# bal2un_1.net
KiCad netlist of a schematic drawn in Altium Designer
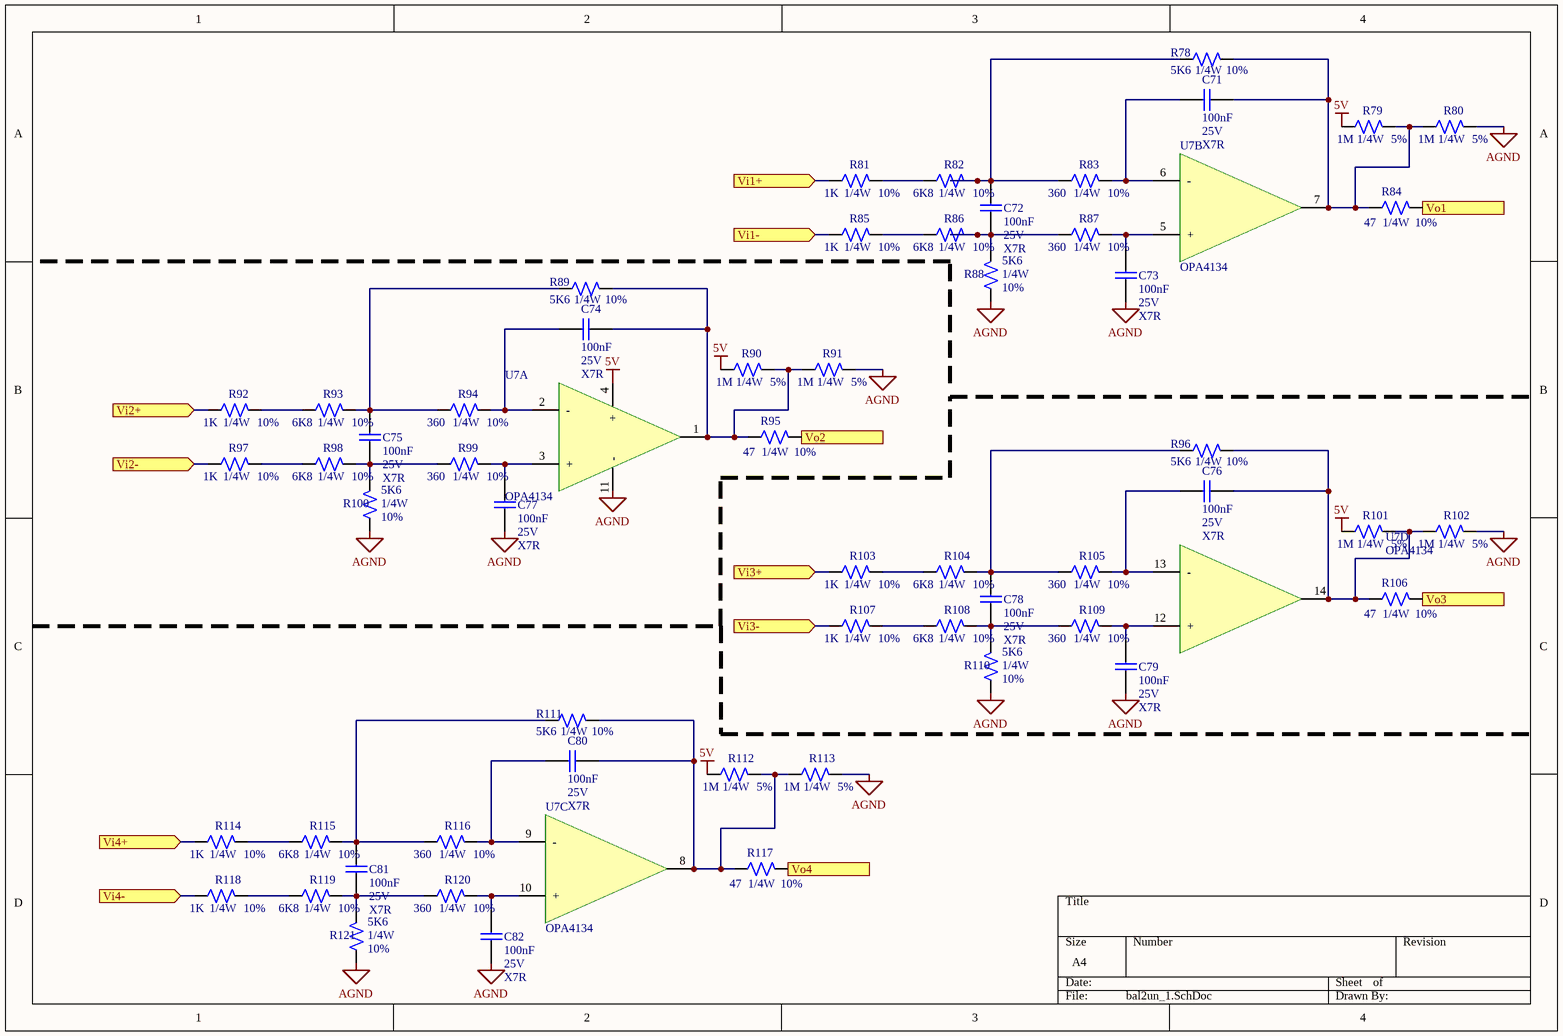
[diagram p0: bal2un_1.SchDoc]

(export (version "E")
  (design (tool "Eeschema 10.0.6"))
  (components
    (comp (ref "C71")
      (value "Capacitor")
      (footprint "C0805")
      (description "Capacitor de placas paralelas")
      (fields (field (name "VALOR") "100nF") (field (name "TENSION") "25V") (field (name "TOLERANCIA") "X7R"))
      (libsource (lib "Sch_Comunes") (part "Capacitor"))
    )
    (comp (ref "C72")
      (value "Capacitor")
      (footprint "C0805")
      (description "Capacitor de placas paralelas")
      (fields (field (name "VALOR") "100nF") (field (name "TENSION") "25V") (field (name "TOLERANCIA") "X7R"))
      (libsource (lib "Sch_Comunes") (part "Capacitor"))
    )
    (comp (ref "C73")
      (value "Capacitor")
      (footprint "C0805")
      (description "Capacitor de placas paralelas")
      (fields (field (name "VALOR") "100nF") (field (name "TENSION") "25V") (field (name "TOLERANCIA") "X7R"))
      (libsource (lib "Sch_Comunes") (part "Capacitor"))
    )
    (comp (ref "C74")
      (value "Capacitor")
      (footprint "C0805")
      (description "Capacitor de placas paralelas")
      (fields (field (name "VALOR") "100nF") (field (name "TENSION") "25V") (field (name "TOLERANCIA") "X7R"))
      (libsource (lib "Sch_Comunes") (part "Capacitor"))
    )
    (comp (ref "C75")
      (value "Capacitor")
      (footprint "C0805")
      (description "Capacitor de placas paralelas")
      (fields (field (name "VALOR") "100nF") (field (name "TENSION") "25V") (field (name "TOLERANCIA") "X7R"))
      (libsource (lib "Sch_Comunes") (part "Capacitor"))
    )
    (comp (ref "C76")
      (value "Capacitor")
      (footprint "C0805")
      (description "Capacitor de placas paralelas")
      (fields (field (name "VALOR") "100nF") (field (name "TENSION") "25V") (field (name "TOLERANCIA") "X7R"))
      (libsource (lib "Sch_Comunes") (part "Capacitor"))
    )
    (comp (ref "C77")
      (value "Capacitor")
      (footprint "C0805")
      (description "Capacitor de placas paralelas")
      (fields (field (name "VALOR") "100nF") (field (name "TENSION") "25V") (field (name "TOLERANCIA") "X7R"))
      (libsource (lib "Sch_Comunes") (part "Capacitor"))
    )
    (comp (ref "C78")
      (value "Capacitor")
      (footprint "C0805")
      (description "Capacitor de placas paralelas")
      (fields (field (name "VALOR") "100nF") (field (name "TENSION") "25V") (field (name "TOLERANCIA") "X7R"))
      (libsource (lib "Sch_Comunes") (part "Capacitor"))
    )
    (comp (ref "C79")
      (value "Capacitor")
      (footprint "C0805")
      (description "Capacitor de placas paralelas")
      (fields (field (name "VALOR") "100nF") (field (name "TENSION") "25V") (field (name "TOLERANCIA") "X7R"))
      (libsource (lib "Sch_Comunes") (part "Capacitor"))
    )
    (comp (ref "C80")
      (value "Capacitor")
      (footprint "C0805")
      (description "Capacitor de placas paralelas")
      (fields (field (name "VALOR") "100nF") (field (name "TENSION") "25V") (field (name "TOLERANCIA") "X7R"))
      (libsource (lib "Sch_Comunes") (part "Capacitor"))
    )
    (comp (ref "C81")
      (value "Capacitor")
      (footprint "C0805")
      (description "Capacitor de placas paralelas")
      (fields (field (name "VALOR") "100nF") (field (name "TENSION") "25V") (field (name "TOLERANCIA") "X7R"))
      (libsource (lib "Sch_Comunes") (part "Capacitor"))
    )
    (comp (ref "C82")
      (value "Capacitor")
      (footprint "C0805")
      (description "Capacitor de placas paralelas")
      (fields (field (name "VALOR") "100nF") (field (name "TENSION") "25V") (field (name "TOLERANCIA") "X7R"))
      (libsource (lib "Sch_Comunes") (part "Capacitor"))
    )
    (comp (ref "R78")
      (value "Resistor")
      (footprint "R0805")
      (description "Resistencia")
      (fields (field (name "VALOR") "5K6") (field (name "POTENCIA") "1/4W") (field (name "TOLERANCIA") "10%"))
      (libsource (lib "sch_comunes") (part "Resistor"))
    )
    (comp (ref "R79")
      (value "Resistor")
      (footprint "R0805")
      (description "Resistencia")
      (fields (field (name "VALOR") "1M") (field (name "POTENCIA") "1/4W") (field (name "TOLERANCIA") "5%"))
      (libsource (lib "sch_comunes") (part "Resistor"))
    )
    (comp (ref "R80")
      (value "Resistor")
      (footprint "R0805")
      (description "Resistencia")
      (fields (field (name "VALOR") "1M") (field (name "POTENCIA") "1/4W") (field (name "TOLERANCIA") "5%"))
      (libsource (lib "sch_comunes") (part "Resistor"))
    )
    (comp (ref "R81")
      (value "Resistor")
      (footprint "R0805")
      (description "Resistencia")
      (fields (field (name "VALOR") "1K") (field (name "POTENCIA") "1/4W") (field (name "TOLERANCIA") "10%"))
      (libsource (lib "sch_comunes") (part "Resistor"))
    )
    (comp (ref "R82")
      (value "Resistor")
      (footprint "R0805")
      (description "Resistencia")
      (fields (field (name "VALOR") "6K8") (field (name "POTENCIA") "1/4W") (field (name "TOLERANCIA") "10%"))
      (libsource (lib "sch_comunes") (part "Resistor"))
    )
    (comp (ref "R83")
      (value "Resistor")
      (footprint "R0805")
      (description "Resistencia")
      (fields (field (name "VALOR") "360") (field (name "POTENCIA") "1/4W") (field (name "TOLERANCIA") "10%"))
      (libsource (lib "sch_comunes") (part "Resistor"))
    )
    (comp (ref "R84")
      (value "Resistor")
      (footprint "R0805")
      (description "Resistencia")
      (fields (field (name "VALOR") "47") (field (name "POTENCIA") "1/4W") (field (name "TOLERANCIA") "10%"))
      (libsource (lib "sch_comunes") (part "Resistor"))
    )
    (comp (ref "R85")
      (value "Resistor")
      (footprint "R0805")
      (description "Resistencia")
      (fields (field (name "VALOR") "1K") (field (name "POTENCIA") "1/4W") (field (name "TOLERANCIA") "10%"))
      (libsource (lib "sch_comunes") (part "Resistor"))
    )
    (comp (ref "R86")
      (value "Resistor")
      (footprint "R0805")
      (description "Resistencia")
      (fields (field (name "VALOR") "6K8") (field (name "POTENCIA") "1/4W") (field (name "TOLERANCIA") "10%"))
      (libsource (lib "sch_comunes") (part "Resistor"))
    )
    (comp (ref "R87")
      (value "Resistor")
      (footprint "R0805")
      (description "Resistencia")
      (fields (field (name "VALOR") "360") (field (name "POTENCIA") "1/4W") (field (name "TOLERANCIA") "10%"))
      (libsource (lib "sch_comunes") (part "Resistor"))
    )
    (comp (ref "R88")
      (value "Resistor")
      (footprint "R0805")
      (description "Resistencia")
      (fields (field (name "VALOR") "5K6") (field (name "POTENCIA") "1/4W") (field (name "TOLERANCIA") "10%"))
      (libsource (lib "sch_comunes") (part "Resistor"))
    )
    (comp (ref "R89")
      (value "Resistor")
      (footprint "R0805")
      (description "Resistencia")
      (fields (field (name "VALOR") "5K6") (field (name "POTENCIA") "1/4W") (field (name "TOLERANCIA") "10%"))
      (libsource (lib "sch_comunes") (part "Resistor"))
    )
    (comp (ref "R90")
      (value "Resistor")
      (footprint "R0805")
      (description "Resistencia")
      (fields (field (name "VALOR") "1M") (field (name "POTENCIA") "1/4W") (field (name "TOLERANCIA") "5%"))
      (libsource (lib "sch_comunes") (part "Resistor"))
    )
    (comp (ref "R91")
      (value "Resistor")
      (footprint "R0805")
      (description "Resistencia")
      (fields (field (name "VALOR") "1M") (field (name "POTENCIA") "1/4W") (field (name "TOLERANCIA") "5%"))
      (libsource (lib "sch_comunes") (part "Resistor"))
    )
    (comp (ref "R92")
      (value "Resistor")
      (footprint "R0805")
      (description "Resistencia")
      (fields (field (name "VALOR") "1K") (field (name "POTENCIA") "1/4W") (field (name "TOLERANCIA") "10%"))
      (libsource (lib "sch_comunes") (part "Resistor"))
    )
    (comp (ref "R93")
      (value "Resistor")
      (footprint "R0805")
      (description "Resistencia")
      (fields (field (name "VALOR") "6K8") (field (name "POTENCIA") "1/4W") (field (name "TOLERANCIA") "10%"))
      (libsource (lib "sch_comunes") (part "Resistor"))
    )
    (comp (ref "R94")
      (value "Resistor")
      (footprint "R0805")
      (description "Resistencia")
      (fields (field (name "VALOR") "360") (field (name "POTENCIA") "1/4W") (field (name "TOLERANCIA") "10%"))
      (libsource (lib "sch_comunes") (part "Resistor"))
    )
    (comp (ref "R95")
      (value "Resistor")
      (footprint "R0805")
      (description "Resistencia")
      (fields (field (name "VALOR") "47") (field (name "POTENCIA") "1/4W") (field (name "TOLERANCIA") "10%"))
      (libsource (lib "sch_comunes") (part "Resistor"))
    )
    (comp (ref "R96")
      (value "Resistor")
      (footprint "R0805")
      (description "Resistencia")
      (fields (field (name "VALOR") "5K6") (field (name "POTENCIA") "1/4W") (field (name "TOLERANCIA") "10%"))
      (libsource (lib "sch_comunes") (part "Resistor"))
    )
    (comp (ref "R97")
      (value "Resistor")
      (footprint "R0805")
      (description "Resistencia")
      (fields (field (name "VALOR") "1K") (field (name "POTENCIA") "1/4W") (field (name "TOLERANCIA") "10%"))
      (libsource (lib "sch_comunes") (part "Resistor"))
    )
    (comp (ref "R98")
      (value "Resistor")
      (footprint "R0805")
      (description "Resistencia")
      (fields (field (name "VALOR") "6K8") (field (name "POTENCIA") "1/4W") (field (name "TOLERANCIA") "10%"))
      (libsource (lib "sch_comunes") (part "Resistor"))
    )
    (comp (ref "R99")
      (value "Resistor")
      (footprint "R0805")
      (description "Resistencia")
      (fields (field (name "VALOR") "360") (field (name "POTENCIA") "1/4W") (field (name "TOLERANCIA") "10%"))
      (libsource (lib "sch_comunes") (part "Resistor"))
    )
    (comp (ref "R100")
      (value "Resistor")
      (footprint "R0805")
      (description "Resistencia")
      (fields (field (name "VALOR") "5K6") (field (name "POTENCIA") "1/4W") (field (name "TOLERANCIA") "10%"))
      (libsource (lib "sch_comunes") (part "Resistor"))
    )
    (comp (ref "R101")
      (value "Resistor")
      (footprint "R0805")
      (description "Resistencia")
      (fields (field (name "VALOR") "1M") (field (name "POTENCIA") "1/4W") (field (name "TOLERANCIA") "5%"))
      (libsource (lib "sch_comunes") (part "Resistor"))
    )
    (comp (ref "R102")
      (value "Resistor")
      (footprint "R0805")
      (description "Resistencia")
      (fields (field (name "VALOR") "1M") (field (name "POTENCIA") "1/4W") (field (name "TOLERANCIA") "5%"))
      (libsource (lib "sch_comunes") (part "Resistor"))
    )
    (comp (ref "R103")
      (value "Resistor")
      (footprint "R0805")
      (description "Resistencia")
      (fields (field (name "VALOR") "1K") (field (name "POTENCIA") "1/4W") (field (name "TOLERANCIA") "10%"))
      (libsource (lib "sch_comunes") (part "Resistor"))
    )
    (comp (ref "R104")
      (value "Resistor")
      (footprint "R0805")
      (description "Resistencia")
      (fields (field (name "VALOR") "6K8") (field (name "POTENCIA") "1/4W") (field (name "TOLERANCIA") "10%"))
      (libsource (lib "sch_comunes") (part "Resistor"))
    )
    (comp (ref "R105")
      (value "Resistor")
      (footprint "R0805")
      (description "Resistencia")
      (fields (field (name "VALOR") "360") (field (name "POTENCIA") "1/4W") (field (name "TOLERANCIA") "10%"))
      (libsource (lib "sch_comunes") (part "Resistor"))
    )
    (comp (ref "R106")
      (value "Resistor")
      (footprint "R0805")
      (description "Resistencia")
      (fields (field (name "VALOR") "47") (field (name "POTENCIA") "1/4W") (field (name "TOLERANCIA") "10%"))
      (libsource (lib "sch_comunes") (part "Resistor"))
    )
    (comp (ref "R107")
      (value "Resistor")
      (footprint "R0805")
      (description "Resistencia")
      (fields (field (name "VALOR") "1K") (field (name "POTENCIA") "1/4W") (field (name "TOLERANCIA") "10%"))
      (libsource (lib "sch_comunes") (part "Resistor"))
    )
    (comp (ref "R108")
      (value "Resistor")
      (footprint "R0805")
      (description "Resistencia")
      (fields (field (name "VALOR") "6K8") (field (name "POTENCIA") "1/4W") (field (name "TOLERANCIA") "10%"))
      (libsource (lib "sch_comunes") (part "Resistor"))
    )
    (comp (ref "R109")
      (value "Resistor")
      (footprint "R0805")
      (description "Resistencia")
      (fields (field (name "VALOR") "360") (field (name "POTENCIA") "1/4W") (field (name "TOLERANCIA") "10%"))
      (libsource (lib "sch_comunes") (part "Resistor"))
    )
    (comp (ref "R110")
      (value "Resistor")
      (footprint "R0805")
      (description "Resistencia")
      (fields (field (name "VALOR") "5K6") (field (name "POTENCIA") "1/4W") (field (name "TOLERANCIA") "10%"))
      (libsource (lib "sch_comunes") (part "Resistor"))
    )
    (comp (ref "R111")
      (value "Resistor")
      (footprint "R0805")
      (description "Resistencia")
      (fields (field (name "VALOR") "5K6") (field (name "POTENCIA") "1/4W") (field (name "TOLERANCIA") "10%"))
      (libsource (lib "sch_comunes") (part "Resistor"))
    )
    (comp (ref "R112")
      (value "Resistor")
      (footprint "R0805")
      (description "Resistencia")
      (fields (field (name "VALOR") "1M") (field (name "POTENCIA") "1/4W") (field (name "TOLERANCIA") "5%"))
      (libsource (lib "sch_comunes") (part "Resistor"))
    )
    (comp (ref "R113")
      (value "Resistor")
      (footprint "R0805")
      (description "Resistencia")
      (fields (field (name "VALOR") "1M") (field (name "POTENCIA") "1/4W") (field (name "TOLERANCIA") "5%"))
      (libsource (lib "sch_comunes") (part "Resistor"))
    )
    (comp (ref "R114")
      (value "Resistor")
      (footprint "R0805")
      (description "Resistencia")
      (fields (field (name "VALOR") "1K") (field (name "POTENCIA") "1/4W") (field (name "TOLERANCIA") "10%"))
      (libsource (lib "sch_comunes") (part "Resistor"))
    )
    (comp (ref "R115")
      (value "Resistor")
      (footprint "R0805")
      (description "Resistencia")
      (fields (field (name "VALOR") "6K8") (field (name "POTENCIA") "1/4W") (field (name "TOLERANCIA") "10%"))
      (libsource (lib "sch_comunes") (part "Resistor"))
    )
    (comp (ref "R116")
      (value "Resistor")
      (footprint "R0805")
      (description "Resistencia")
      (fields (field (name "VALOR") "360") (field (name "POTENCIA") "1/4W") (field (name "TOLERANCIA") "10%"))
      (libsource (lib "sch_comunes") (part "Resistor"))
    )
    (comp (ref "R117")
      (value "Resistor")
      (footprint "R0805")
      (description "Resistencia")
      (fields (field (name "VALOR") "47") (field (name "POTENCIA") "1/4W") (field (name "TOLERANCIA") "10%"))
      (libsource (lib "sch_comunes") (part "Resistor"))
    )
    (comp (ref "R118")
      (value "Resistor")
      (footprint "R0805")
      (description "Resistencia")
      (fields (field (name "VALOR") "1K") (field (name "POTENCIA") "1/4W") (field (name "TOLERANCIA") "10%"))
      (libsource (lib "sch_comunes") (part "Resistor"))
    )
    (comp (ref "R119")
      (value "Resistor")
      (footprint "R0805")
      (description "Resistencia")
      (fields (field (name "VALOR") "6K8") (field (name "POTENCIA") "1/4W") (field (name "TOLERANCIA") "10%"))
      (libsource (lib "sch_comunes") (part "Resistor"))
    )
    (comp (ref "R120")
      (value "Resistor")
      (footprint "R0805")
      (description "Resistencia")
      (fields (field (name "VALOR") "360") (field (name "POTENCIA") "1/4W") (field (name "TOLERANCIA") "10%"))
      (libsource (lib "sch_comunes") (part "Resistor"))
    )
    (comp (ref "R121")
      (value "Resistor")
      (footprint "R0805")
      (description "Resistencia")
      (fields (field (name "VALOR") "5K6") (field (name "POTENCIA") "1/4W") (field (name "TOLERANCIA") "10%"))
      (libsource (lib "sch_comunes") (part "Resistor"))
    )
    (comp (ref "U7")
      (value "OPA4134")
      (footprint "TSSOP-14")
      (description "Integrado con 4 operacionales")
      (libsource (lib "sch_opamp") (part "Opamp_x4"))
    )
  )
  (nets
    (net (code "1") (name "/Vi1+") (class "Default")
      (node (ref "R81") (pin "1") (pinfunction "1_1") (pintype "passive"))
    )
    (net (code "2") (name "/Vi1-") (class "Default")
      (node (ref "R85") (pin "1") (pinfunction "1_1") (pintype "passive"))
    )
    (net (code "3") (name "/Vi2+") (class "Default")
      (node (ref "R92") (pin "1") (pinfunction "1_1") (pintype "passive"))
    )
    (net (code "4") (name "/Vi2-") (class "Default")
      (node (ref "R97") (pin "1") (pinfunction "1_1") (pintype "passive"))
    )
    (net (code "5") (name "/Vi3+") (class "Default")
      (node (ref "R103") (pin "1") (pinfunction "1_1") (pintype "passive"))
    )
    (net (code "6") (name "/Vi3-") (class "Default")
      (node (ref "R107") (pin "1") (pinfunction "1_1") (pintype "passive"))
    )
    (net (code "7") (name "/Vi4+") (class "Default")
      (node (ref "R114") (pin "1") (pinfunction "1_1") (pintype "passive"))
    )
    (net (code "8") (name "/Vi4-") (class "Default")
      (node (ref "R118") (pin "1") (pinfunction "1_1") (pintype "passive"))
    )
    (net (code "9") (name "/Vo1") (class "Default")
      (node (ref "R84") (pin "2") (pinfunction "2_2") (pintype "passive"))
    )
    (net (code "10") (name "/Vo2") (class "Default")
      (node (ref "R95") (pin "2") (pinfunction "2_2") (pintype "passive"))
    )
    (net (code "11") (name "/Vo3") (class "Default")
      (node (ref "R106") (pin "2") (pinfunction "2_2") (pintype "passive"))
    )
    (net (code "12") (name "/Vo4") (class "Default")
      (node (ref "R117") (pin "2") (pinfunction "2_2") (pintype "passive"))
    )
    (net (code "13") (name "5V") (class "Default")
      (node (ref "R101") (pin "1") (pinfunction "1_1") (pintype "passive"))
      (node (ref "R112") (pin "1") (pinfunction "1_1") (pintype "passive"))
      (node (ref "R79") (pin "1") (pinfunction "1_1") (pintype "passive"))
      (node (ref "R90") (pin "1") (pinfunction "1_1") (pintype "passive"))
      (node (ref "U7") (pin "4") (pinfunction "+_4") (pintype "power_in"))
    )
    (net (code "14") (name "AGND") (class "Default")
      (node (ref "C73") (pin "2") (pinfunction "2_2") (pintype "passive"))
      (node (ref "C77") (pin "2") (pinfunction "2_2") (pintype "passive"))
      (node (ref "C79") (pin "2") (pinfunction "2_2") (pintype "passive"))
      (node (ref "C82") (pin "2") (pinfunction "2_2") (pintype "passive"))
      (node (ref "R100") (pin "1") (pinfunction "1_1") (pintype "passive"))
      (node (ref "R102") (pin "2") (pinfunction "2_2") (pintype "passive"))
      (node (ref "R110") (pin "1") (pinfunction "1_1") (pintype "passive"))
      (node (ref "R113") (pin "2") (pinfunction "2_2") (pintype "passive"))
      (node (ref "R121") (pin "1") (pinfunction "1_1") (pintype "passive"))
      (node (ref "R80") (pin "2") (pinfunction "2_2") (pintype "passive"))
      (node (ref "R88") (pin "1") (pinfunction "1_1") (pintype "passive"))
      (node (ref "R91") (pin "2") (pinfunction "2_2") (pintype "passive"))
      (node (ref "U7") (pin "11") (pinfunction "-_11") (pintype "passive"))
    )
    (net (code "15") (name "Net-(C72-Pad1)") (class "Default")
      (node (ref "C72") (pin "1") (pinfunction "1_1") (pintype "passive"))
      (node (ref "R78") (pin "1") (pinfunction "1_1") (pintype "passive"))
      (node (ref "R82") (pin "2") (pinfunction "2_2") (pintype "passive"))
      (node (ref "R83") (pin "1") (pinfunction "1_1") (pintype "passive"))
    )
    (net (code "16") (name "Net-(C72-Pad2)") (class "Default")
      (node (ref "C72") (pin "2") (pinfunction "2_2") (pintype "passive"))
      (node (ref "R86") (pin "2") (pinfunction "2_2") (pintype "passive"))
      (node (ref "R87") (pin "1") (pinfunction "1_1") (pintype "passive"))
      (node (ref "R88") (pin "2") (pinfunction "2_2") (pintype "passive"))
    )
    (net (code "17") (name "Net-(C74-Pad2)") (class "Default")
      (node (ref "C74") (pin "2") (pinfunction "2_2") (pintype "passive"))
      (node (ref "R94") (pin "2") (pinfunction "2_2") (pintype "passive"))
      (node (ref "U7") (pin "2") (pinfunction "-_2") (pintype "passive"))
    )
    (net (code "18") (name "Net-(C75-Pad1)") (class "Default")
      (node (ref "C75") (pin "1") (pinfunction "1_1") (pintype "passive"))
      (node (ref "R89") (pin "1") (pinfunction "1_1") (pintype "passive"))
      (node (ref "R93") (pin "2") (pinfunction "2_2") (pintype "passive"))
      (node (ref "R94") (pin "1") (pinfunction "1_1") (pintype "passive"))
    )
    (net (code "19") (name "Net-(C75-Pad2)") (class "Default")
      (node (ref "C75") (pin "2") (pinfunction "2_2") (pintype "passive"))
      (node (ref "R100") (pin "2") (pinfunction "2_2") (pintype "passive"))
      (node (ref "R98") (pin "2") (pinfunction "2_2") (pintype "passive"))
      (node (ref "R99") (pin "1") (pinfunction "1_1") (pintype "passive"))
    )
    (net (code "20") (name "Net-(C77-Pad1)") (class "Default")
      (node (ref "C77") (pin "1") (pinfunction "1_1") (pintype "passive"))
      (node (ref "R99") (pin "2") (pinfunction "2_2") (pintype "passive"))
      (node (ref "U7") (pin "3") (pinfunction "+_3") (pintype "passive"))
    )
    (net (code "21") (name "Net-(C78-Pad1)") (class "Default")
      (node (ref "C78") (pin "1") (pinfunction "1_1") (pintype "passive"))
      (node (ref "R104") (pin "2") (pinfunction "2_2") (pintype "passive"))
      (node (ref "R105") (pin "1") (pinfunction "1_1") (pintype "passive"))
      (node (ref "R96") (pin "1") (pinfunction "1_1") (pintype "passive"))
    )
    (net (code "22") (name "Net-(C78-Pad2)") (class "Default")
      (node (ref "C78") (pin "2") (pinfunction "2_2") (pintype "passive"))
      (node (ref "R108") (pin "2") (pinfunction "2_2") (pintype "passive"))
      (node (ref "R109") (pin "1") (pinfunction "1_1") (pintype "passive"))
      (node (ref "R110") (pin "2") (pinfunction "2_2") (pintype "passive"))
    )
    (net (code "23") (name "Net-(C81-Pad1)") (class "Default")
      (node (ref "C81") (pin "1") (pinfunction "1_1") (pintype "passive"))
      (node (ref "R111") (pin "1") (pinfunction "1_1") (pintype "passive"))
      (node (ref "R115") (pin "2") (pinfunction "2_2") (pintype "passive"))
      (node (ref "R116") (pin "1") (pinfunction "1_1") (pintype "passive"))
    )
    (net (code "24") (name "Net-(C81-Pad2)") (class "Default")
      (node (ref "C81") (pin "2") (pinfunction "2_2") (pintype "passive"))
      (node (ref "R119") (pin "2") (pinfunction "2_2") (pintype "passive"))
      (node (ref "R120") (pin "1") (pinfunction "1_1") (pintype "passive"))
      (node (ref "R121") (pin "2") (pinfunction "2_2") (pintype "passive"))
    )
    (net (code "25") (name "Net-(R81-Pad2)") (class "Default")
      (node (ref "R81") (pin "2") (pinfunction "2_2") (pintype "passive"))
      (node (ref "R82") (pin "1") (pinfunction "1_1") (pintype "passive"))
    )
    (net (code "26") (name "Net-(R85-Pad2)") (class "Default")
      (node (ref "R85") (pin "2") (pinfunction "2_2") (pintype "passive"))
      (node (ref "R86") (pin "1") (pinfunction "1_1") (pintype "passive"))
    )
    (net (code "27") (name "Net-(R92-Pad2)") (class "Default")
      (node (ref "R92") (pin "2") (pinfunction "2_2") (pintype "passive"))
      (node (ref "R93") (pin "1") (pinfunction "1_1") (pintype "passive"))
    )
    (net (code "28") (name "Net-(R97-Pad2)") (class "Default")
      (node (ref "R97") (pin "2") (pinfunction "2_2") (pintype "passive"))
      (node (ref "R98") (pin "1") (pinfunction "1_1") (pintype "passive"))
    )
    (net (code "29") (name "Net-(R103-Pad2)") (class "Default")
      (node (ref "R103") (pin "2") (pinfunction "2_2") (pintype "passive"))
      (node (ref "R104") (pin "1") (pinfunction "1_1") (pintype "passive"))
    )
    (net (code "30") (name "Net-(R107-Pad2)") (class "Default")
      (node (ref "R107") (pin "2") (pinfunction "2_2") (pintype "passive"))
      (node (ref "R108") (pin "1") (pinfunction "1_1") (pintype "passive"))
    )
    (net (code "31") (name "Net-(R114-Pad2)") (class "Default")
      (node (ref "R114") (pin "2") (pinfunction "2_2") (pintype "passive"))
      (node (ref "R115") (pin "1") (pinfunction "1_1") (pintype "passive"))
    )
    (net (code "32") (name "Net-(R118-Pad2)") (class "Default")
      (node (ref "R118") (pin "2") (pinfunction "2_2") (pintype "passive"))
      (node (ref "R119") (pin "1") (pinfunction "1_1") (pintype "passive"))
    )
    (net (code "33") (name "Net-(U7A-OUT)") (class "Default")
      (node (ref "C74") (pin "1") (pinfunction "1_1") (pintype "passive"))
      (node (ref "R89") (pin "2") (pinfunction "2_2") (pintype "passive"))
      (node (ref "R90") (pin "2") (pinfunction "2_2") (pintype "passive"))
      (node (ref "R91") (pin "1") (pinfunction "1_1") (pintype "passive"))
      (node (ref "R95") (pin "1") (pinfunction "1_1") (pintype "passive"))
      (node (ref "U7") (pin "1") (pinfunction "OUT_1") (pintype "passive"))
    )
    (net (code "34") (name "Net-(U7B-+)") (class "Default")
      (node (ref "C73") (pin "1") (pinfunction "1_1") (pintype "passive"))
      (node (ref "R87") (pin "2") (pinfunction "2_2") (pintype "passive"))
      (node (ref "U7") (pin "5") (pinfunction "+_5") (pintype "passive"))
    )
    (net (code "35") (name "Net-(U7B--)") (class "Default")
      (node (ref "C71") (pin "2") (pinfunction "2_2") (pintype "passive"))
      (node (ref "R83") (pin "2") (pinfunction "2_2") (pintype "passive"))
      (node (ref "U7") (pin "6") (pinfunction "-_6") (pintype "passive"))
    )
    (net (code "36") (name "Net-(U7B-OUT)") (class "Default")
      (node (ref "C71") (pin "1") (pinfunction "1_1") (pintype "passive"))
      (node (ref "R78") (pin "2") (pinfunction "2_2") (pintype "passive"))
      (node (ref "R79") (pin "2") (pinfunction "2_2") (pintype "passive"))
      (node (ref "R80") (pin "1") (pinfunction "1_1") (pintype "passive"))
      (node (ref "R84") (pin "1") (pinfunction "1_1") (pintype "passive"))
      (node (ref "U7") (pin "7") (pinfunction "OUT_7") (pintype "passive"))
    )
    (net (code "37") (name "Net-(U7C-+)") (class "Default")
      (node (ref "C82") (pin "1") (pinfunction "1_1") (pintype "passive"))
      (node (ref "R120") (pin "2") (pinfunction "2_2") (pintype "passive"))
      (node (ref "U7") (pin "10") (pinfunction "+_10") (pintype "passive"))
    )
    (net (code "38") (name "Net-(U7C--)") (class "Default")
      (node (ref "C80") (pin "2") (pinfunction "2_2") (pintype "passive"))
      (node (ref "R116") (pin "2") (pinfunction "2_2") (pintype "passive"))
      (node (ref "U7") (pin "9") (pinfunction "-_9") (pintype "passive"))
    )
    (net (code "39") (name "Net-(U7C-OUT)") (class "Default")
      (node (ref "C80") (pin "1") (pinfunction "1_1") (pintype "passive"))
      (node (ref "R111") (pin "2") (pinfunction "2_2") (pintype "passive"))
      (node (ref "R112") (pin "2") (pinfunction "2_2") (pintype "passive"))
      (node (ref "R113") (pin "1") (pinfunction "1_1") (pintype "passive"))
      (node (ref "R117") (pin "1") (pinfunction "1_1") (pintype "passive"))
      (node (ref "U7") (pin "8") (pinfunction "OUT_8") (pintype "passive"))
    )
    (net (code "40") (name "Net-(U7D-+)") (class "Default")
      (node (ref "C79") (pin "1") (pinfunction "1_1") (pintype "passive"))
      (node (ref "R109") (pin "2") (pinfunction "2_2") (pintype "passive"))
      (node (ref "U7") (pin "12") (pinfunction "+_12") (pintype "passive"))
    )
    (net (code "41") (name "Net-(U7D--)") (class "Default")
      (node (ref "C76") (pin "2") (pinfunction "2_2") (pintype "passive"))
      (node (ref "R105") (pin "2") (pinfunction "2_2") (pintype "passive"))
      (node (ref "U7") (pin "13") (pinfunction "-_13") (pintype "passive"))
    )
    (net (code "42") (name "Net-(U7D-OUT)") (class "Default")
      (node (ref "C76") (pin "1") (pinfunction "1_1") (pintype "passive"))
      (node (ref "R101") (pin "2") (pinfunction "2_2") (pintype "passive"))
      (node (ref "R102") (pin "1") (pinfunction "1_1") (pintype "passive"))
      (node (ref "R106") (pin "1") (pinfunction "1_1") (pintype "passive"))
      (node (ref "R96") (pin "2") (pinfunction "2_2") (pintype "passive"))
      (node (ref "U7") (pin "14") (pinfunction "OUT_14") (pintype "passive"))
    )
  )
)
